# Nixie.net
KiCad netlist of a schematic drawn in Altium Designer
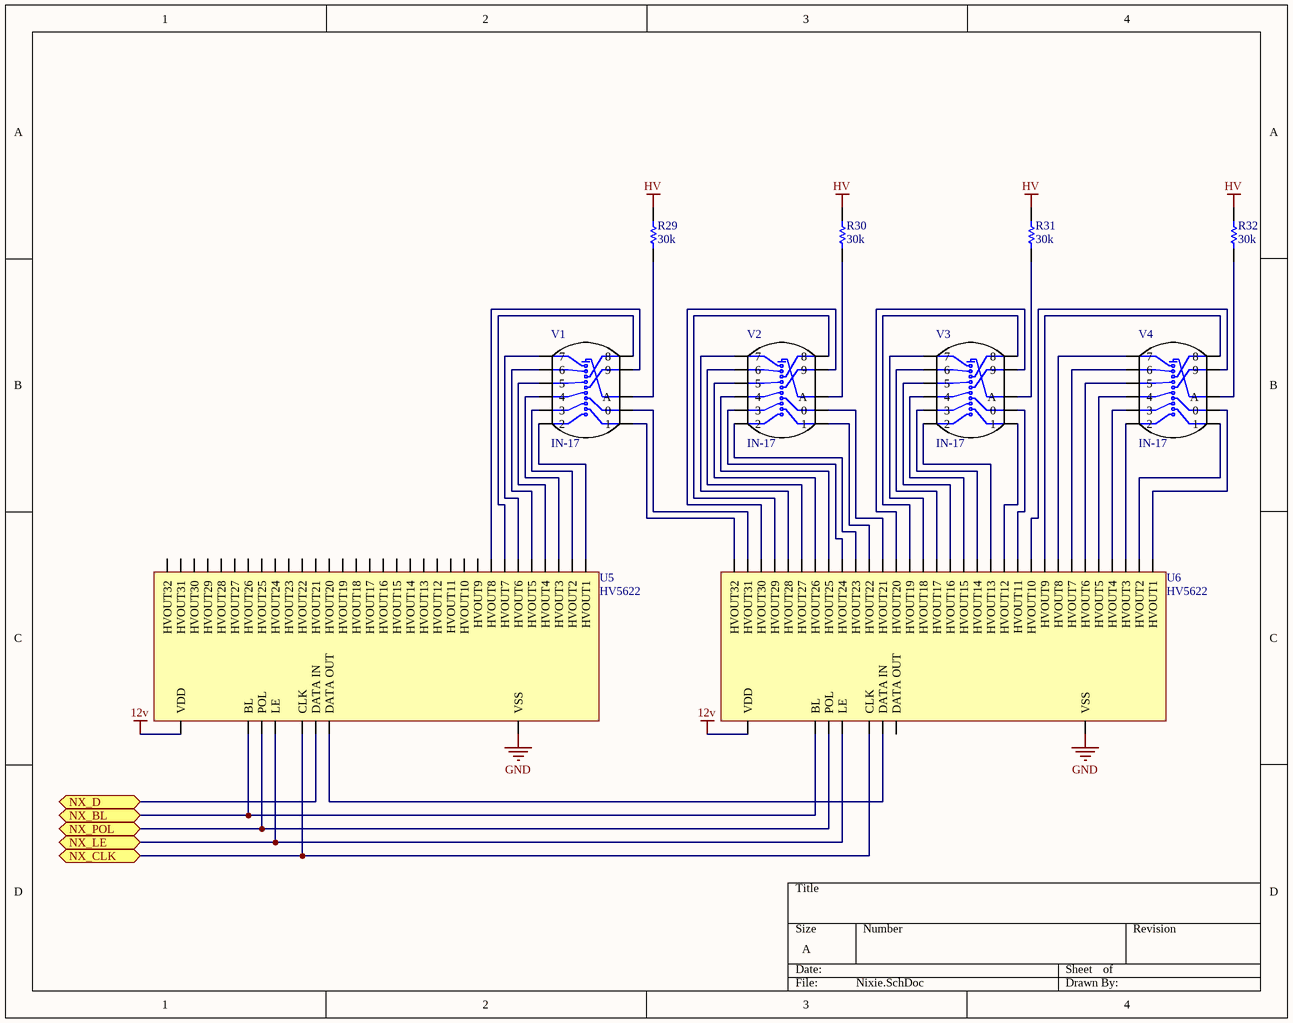
[diagram p0: Nixie.SchDoc]

(export (version "E")
  (design (tool "Eeschema 10.0.6"))
  (components
    (comp (ref "R29")
      (value "30k")
      (footprint "R0805")
      (description "RES SMD 30K OHM 5% 1/8W 0805")
      (libsource (lib "Schlib1") (part "30k 0805 5%"))
    )
    (comp (ref "R30")
      (value "30k")
      (footprint "R0805")
      (description "RES SMD 30K OHM 5% 1/8W 0805")
      (libsource (lib "Schlib1") (part "30k 0805 5%"))
    )
    (comp (ref "R31")
      (value "30k")
      (footprint "R0805")
      (description "RES SMD 30K OHM 5% 1/8W 0805")
      (libsource (lib "Schlib1") (part "30k 0805 5%"))
    )
    (comp (ref "R32")
      (value "30k")
      (footprint "R0805")
      (description "RES SMD 30K OHM 5% 1/8W 0805")
      (libsource (lib "Schlib1") (part "30k 0805 5%"))
    )
    (comp (ref "U5")
      (value "HV5622")
      (footprint "44-PQFP")
      (description "IC 32BIT SRL PARALLEL 220V 44PQF")
      (libsource (lib "Schlib1") (part "HV5622"))
    )
    (comp (ref "U6")
      (value "HV5622")
      (footprint "44-PQFP")
      (description "IC 32BIT SRL PARALLEL 220V 44PQF")
      (libsource (lib "Schlib1") (part "HV5622"))
    )
    (comp (ref "V1")
      (value "IN-17")
      (footprint "IN-17")
      (description "IN-17 Nixie Display Tube")
      (libsource (lib "Schlib1") (part "IN-17 Nixie"))
    )
    (comp (ref "V2")
      (value "IN-17")
      (footprint "IN-17")
      (description "IN-17 Nixie Display Tube")
      (libsource (lib "Schlib1") (part "IN-17 Nixie"))
    )
    (comp (ref "V3")
      (value "IN-17")
      (footprint "IN-17")
      (description "IN-17 Nixie Display Tube")
      (libsource (lib "Schlib1") (part "IN-17 Nixie"))
    )
    (comp (ref "V4")
      (value "IN-17")
      (footprint "IN-17")
      (description "IN-17 Nixie Display Tube")
      (libsource (lib "Schlib1") (part "IN-17 Nixie"))
    )
  )
  (nets
    (net (code "1") (name "/NX_BL") (class "Default")
      (node (ref "U5") (pin "33") (pinfunction "BL_33") (pintype "passive"))
      (node (ref "U6") (pin "33") (pinfunction "BL_33") (pintype "passive"))
    )
    (net (code "2") (name "/NX_CLK") (class "Default")
      (node (ref "U5") (pin "28") (pinfunction "CLK_28") (pintype "passive"))
      (node (ref "U6") (pin "28") (pinfunction "CLK_28") (pintype "passive"))
    )
    (net (code "3") (name "/NX_D") (class "Default")
      (node (ref "U5") (pin "32") (pinfunction "DATA_IN_32") (pintype "passive"))
    )
    (net (code "4") (name "/NX_LE") (class "Default")
      (node (ref "U5") (pin "31") (pinfunction "LE_31") (pintype "passive"))
      (node (ref "U6") (pin "31") (pinfunction "LE_31") (pintype "passive"))
    )
    (net (code "5") (name "/NX_POL") (class "Default")
      (node (ref "U5") (pin "27") (pinfunction "POL_27") (pintype "passive"))
      (node (ref "U6") (pin "27") (pinfunction "POL_27") (pintype "passive"))
    )
    (net (code "6") (name "12v") (class "Default")
      (node (ref "U5") (pin "30") (pinfunction "VDD_30") (pintype "passive"))
      (node (ref "U6") (pin "30") (pinfunction "VDD_30") (pintype "passive"))
    )
    (net (code "7") (name "GND") (class "Default")
      (node (ref "U5") (pin "29") (pinfunction "VSS_29") (pintype "passive"))
      (node (ref "U6") (pin "29") (pinfunction "VSS_29") (pintype "passive"))
    )
    (net (code "8") (name "HV") (class "Default")
      (node (ref "R29") (pin "2") (pinfunction "2_2") (pintype "passive"))
      (node (ref "R30") (pin "2") (pinfunction "2_2") (pintype "passive"))
      (node (ref "R31") (pin "2") (pinfunction "2_2") (pintype "passive"))
      (node (ref "R32") (pin "2") (pinfunction "2_2") (pintype "passive"))
    )
    (net (code "9") (name "Net-(U5-DATA_OUT)") (class "Default")
      (node (ref "U5") (pin "23") (pinfunction "DATA_OUT_23") (pintype "passive"))
      (node (ref "U6") (pin "32") (pinfunction "DATA_IN_32") (pintype "passive"))
    )
    (net (code "10") (name "Net-(U5-HVOUT1)") (class "Default")
      (node (ref "U5") (pin "22") (pinfunction "HVOUT1_22") (pintype "passive"))
      (node (ref "V1") (pin "4") (pinfunction "2_4") (pintype "passive"))
    )
    (net (code "11") (name "Net-(U5-HVOUT2)") (class "Default")
      (node (ref "U5") (pin "21") (pinfunction "HVOUT2_21") (pintype "passive"))
      (node (ref "V1") (pin "5") (pinfunction "3_5") (pintype "passive"))
    )
    (net (code "12") (name "Net-(U5-HVOUT3)") (class "Default")
      (node (ref "U5") (pin "20") (pinfunction "HVOUT3_20") (pintype "passive"))
      (node (ref "V1") (pin "6") (pinfunction "4_6") (pintype "passive"))
    )
    (net (code "13") (name "Net-(U5-HVOUT4)") (class "Default")
      (node (ref "U5") (pin "19") (pinfunction "HVOUT4_19") (pintype "passive"))
      (node (ref "V1") (pin "7") (pinfunction "5_7") (pintype "passive"))
    )
    (net (code "14") (name "Net-(U5-HVOUT5)") (class "Default")
      (node (ref "U5") (pin "18") (pinfunction "HVOUT5_18") (pintype "passive"))
      (node (ref "V1") (pin "8") (pinfunction "6_8") (pintype "passive"))
    )
    (net (code "15") (name "Net-(U5-HVOUT6)") (class "Default")
      (node (ref "U5") (pin "17") (pinfunction "HVOUT6_17") (pintype "passive"))
      (node (ref "V1") (pin "9") (pinfunction "7_9") (pintype "passive"))
    )
    (net (code "16") (name "Net-(U5-HVOUT7)") (class "Default")
      (node (ref "U5") (pin "16") (pinfunction "HVOUT7_16") (pintype "passive"))
      (node (ref "V1") (pin "10") (pinfunction "8_10") (pintype "passive"))
    )
    (net (code "17") (name "Net-(U5-HVOUT8)") (class "Default")
      (node (ref "U5") (pin "15") (pinfunction "HVOUT8_15") (pintype "passive"))
      (node (ref "V1") (pin "11") (pinfunction "9_11") (pintype "passive"))
    )
    (net (code "18") (name "Net-(U6-HVOUT1)") (class "Default")
      (node (ref "U6") (pin "22") (pinfunction "HVOUT1_22") (pintype "passive"))
      (node (ref "V4") (pin "2") (pinfunction "0_2") (pintype "passive"))
    )
    (net (code "19") (name "Net-(U6-HVOUT2)") (class "Default")
      (node (ref "U6") (pin "21") (pinfunction "HVOUT2_21") (pintype "passive"))
      (node (ref "V4") (pin "3") (pinfunction "1_3") (pintype "passive"))
    )
    (net (code "20") (name "Net-(U6-HVOUT3)") (class "Default")
      (node (ref "U6") (pin "20") (pinfunction "HVOUT3_20") (pintype "passive"))
      (node (ref "V4") (pin "4") (pinfunction "2_4") (pintype "passive"))
    )
    (net (code "21") (name "Net-(U6-HVOUT4)") (class "Default")
      (node (ref "U6") (pin "19") (pinfunction "HVOUT4_19") (pintype "passive"))
      (node (ref "V4") (pin "5") (pinfunction "3_5") (pintype "passive"))
    )
    (net (code "22") (name "Net-(U6-HVOUT5)") (class "Default")
      (node (ref "U6") (pin "18") (pinfunction "HVOUT5_18") (pintype "passive"))
      (node (ref "V4") (pin "6") (pinfunction "4_6") (pintype "passive"))
    )
    (net (code "23") (name "Net-(U6-HVOUT6)") (class "Default")
      (node (ref "U6") (pin "17") (pinfunction "HVOUT6_17") (pintype "passive"))
      (node (ref "V4") (pin "7") (pinfunction "5_7") (pintype "passive"))
    )
    (net (code "24") (name "Net-(U6-HVOUT7)") (class "Default")
      (node (ref "U6") (pin "16") (pinfunction "HVOUT7_16") (pintype "passive"))
      (node (ref "V4") (pin "8") (pinfunction "6_8") (pintype "passive"))
    )
    (net (code "25") (name "Net-(U6-HVOUT8)") (class "Default")
      (node (ref "U6") (pin "15") (pinfunction "HVOUT8_15") (pintype "passive"))
      (node (ref "V4") (pin "9") (pinfunction "7_9") (pintype "passive"))
    )
    (net (code "26") (name "Net-(U6-HVOUT9)") (class "Default")
      (node (ref "U6") (pin "14") (pinfunction "HVOUT9_14") (pintype "passive"))
      (node (ref "V4") (pin "10") (pinfunction "8_10") (pintype "passive"))
    )
    (net (code "27") (name "Net-(U6-HVOUT10)") (class "Default")
      (node (ref "U6") (pin "13") (pinfunction "HVOUT10_13") (pintype "passive"))
      (node (ref "V4") (pin "11") (pinfunction "9_11") (pintype "passive"))
    )
    (net (code "28") (name "Net-(U6-HVOUT11)") (class "Default")
      (node (ref "U6") (pin "12") (pinfunction "HVOUT11_12") (pintype "passive"))
      (node (ref "V3") (pin "2") (pinfunction "0_2") (pintype "passive"))
    )
    (net (code "29") (name "Net-(U6-HVOUT12)") (class "Default")
      (node (ref "U6") (pin "11") (pinfunction "HVOUT12_11") (pintype "passive"))
      (node (ref "V3") (pin "3") (pinfunction "1_3") (pintype "passive"))
    )
    (net (code "30") (name "Net-(U6-HVOUT13)") (class "Default")
      (node (ref "U6") (pin "10") (pinfunction "HVOUT13_10") (pintype "passive"))
      (node (ref "V3") (pin "4") (pinfunction "2_4") (pintype "passive"))
    )
    (net (code "31") (name "Net-(U6-HVOUT14)") (class "Default")
      (node (ref "U6") (pin "9") (pinfunction "HVOUT14_9") (pintype "passive"))
      (node (ref "V3") (pin "5") (pinfunction "3_5") (pintype "passive"))
    )
    (net (code "32") (name "Net-(U6-HVOUT15)") (class "Default")
      (node (ref "U6") (pin "8") (pinfunction "HVOUT15_8") (pintype "passive"))
      (node (ref "V3") (pin "6") (pinfunction "4_6") (pintype "passive"))
    )
    (net (code "33") (name "Net-(U6-HVOUT16)") (class "Default")
      (node (ref "U6") (pin "7") (pinfunction "HVOUT16_7") (pintype "passive"))
      (node (ref "V3") (pin "7") (pinfunction "5_7") (pintype "passive"))
    )
    (net (code "34") (name "Net-(U6-HVOUT17)") (class "Default")
      (node (ref "U6") (pin "6") (pinfunction "HVOUT17_6") (pintype "passive"))
      (node (ref "V3") (pin "8") (pinfunction "6_8") (pintype "passive"))
    )
    (net (code "35") (name "Net-(U6-HVOUT18)") (class "Default")
      (node (ref "U6") (pin "5") (pinfunction "HVOUT18_5") (pintype "passive"))
      (node (ref "V3") (pin "9") (pinfunction "7_9") (pintype "passive"))
    )
    (net (code "36") (name "Net-(U6-HVOUT19)") (class "Default")
      (node (ref "U6") (pin "4") (pinfunction "HVOUT19_4") (pintype "passive"))
      (node (ref "V3") (pin "10") (pinfunction "8_10") (pintype "passive"))
    )
    (net (code "37") (name "Net-(U6-HVOUT20)") (class "Default")
      (node (ref "U6") (pin "3") (pinfunction "HVOUT20_3") (pintype "passive"))
      (node (ref "V3") (pin "11") (pinfunction "9_11") (pintype "passive"))
    )
    (net (code "38") (name "Net-(U6-HVOUT21)") (class "Default")
      (node (ref "U6") (pin "2") (pinfunction "HVOUT21_2") (pintype "passive"))
      (node (ref "V2") (pin "2") (pinfunction "0_2") (pintype "passive"))
    )
    (net (code "39") (name "Net-(U6-HVOUT22)") (class "Default")
      (node (ref "U6") (pin "1") (pinfunction "HVOUT22_1") (pintype "passive"))
      (node (ref "V2") (pin "3") (pinfunction "1_3") (pintype "passive"))
    )
    (net (code "40") (name "Net-(U6-HVOUT23)") (class "Default")
      (node (ref "U6") (pin "44") (pinfunction "HVOUT23_44") (pintype "passive"))
      (node (ref "V2") (pin "4") (pinfunction "2_4") (pintype "passive"))
    )
    (net (code "41") (name "Net-(U6-HVOUT24)") (class "Default")
      (node (ref "U6") (pin "43") (pinfunction "HVOUT24_43") (pintype "passive"))
      (node (ref "V2") (pin "5") (pinfunction "3_5") (pintype "passive"))
    )
    (net (code "42") (name "Net-(U6-HVOUT25)") (class "Default")
      (node (ref "U6") (pin "42") (pinfunction "HVOUT25_42") (pintype "passive"))
      (node (ref "V2") (pin "6") (pinfunction "4_6") (pintype "passive"))
    )
    (net (code "43") (name "Net-(U6-HVOUT26)") (class "Default")
      (node (ref "U6") (pin "41") (pinfunction "HVOUT26_41") (pintype "passive"))
      (node (ref "V2") (pin "7") (pinfunction "5_7") (pintype "passive"))
    )
    (net (code "44") (name "Net-(U6-HVOUT27)") (class "Default")
      (node (ref "U6") (pin "40") (pinfunction "HVOUT27_40") (pintype "passive"))
      (node (ref "V2") (pin "8") (pinfunction "6_8") (pintype "passive"))
    )
    (net (code "45") (name "Net-(U6-HVOUT28)") (class "Default")
      (node (ref "U6") (pin "39") (pinfunction "HVOUT28_39") (pintype "passive"))
      (node (ref "V2") (pin "9") (pinfunction "7_9") (pintype "passive"))
    )
    (net (code "46") (name "Net-(U6-HVOUT29)") (class "Default")
      (node (ref "U6") (pin "38") (pinfunction "HVOUT29_38") (pintype "passive"))
      (node (ref "V2") (pin "10") (pinfunction "8_10") (pintype "passive"))
    )
    (net (code "47") (name "Net-(U6-HVOUT30)") (class "Default")
      (node (ref "U6") (pin "37") (pinfunction "HVOUT30_37") (pintype "passive"))
      (node (ref "V2") (pin "11") (pinfunction "9_11") (pintype "passive"))
    )
    (net (code "48") (name "Net-(U6-HVOUT31)") (class "Default")
      (node (ref "U6") (pin "36") (pinfunction "HVOUT31_36") (pintype "passive"))
      (node (ref "V1") (pin "2") (pinfunction "0_2") (pintype "passive"))
    )
    (net (code "49") (name "Net-(U6-HVOUT32)") (class "Default")
      (node (ref "U6") (pin "35") (pinfunction "HVOUT32_35") (pintype "passive"))
      (node (ref "V1") (pin "3") (pinfunction "1_3") (pintype "passive"))
    )
    (net (code "50") (name "Net-(V1-A)") (class "Default")
      (node (ref "R29") (pin "1") (pinfunction "1_1") (pintype "passive"))
      (node (ref "V1") (pin "1") (pinfunction "A_1") (pintype "passive"))
    )
    (net (code "51") (name "Net-(V2-A)") (class "Default")
      (node (ref "R30") (pin "1") (pinfunction "1_1") (pintype "passive"))
      (node (ref "V2") (pin "1") (pinfunction "A_1") (pintype "passive"))
    )
    (net (code "52") (name "Net-(V3-A)") (class "Default")
      (node (ref "R31") (pin "1") (pinfunction "1_1") (pintype "passive"))
      (node (ref "V3") (pin "1") (pinfunction "A_1") (pintype "passive"))
    )
    (net (code "53") (name "Net-(V4-A)") (class "Default")
      (node (ref "R32") (pin "1") (pinfunction "1_1") (pintype "passive"))
      (node (ref "V4") (pin "1") (pinfunction "A_1") (pintype "passive"))
    )
    (net (code "54") (name "unconnected-(U5-HVOUT9-Pad14)") (class "Default")
      (node (ref "U5") (pin "14") (pinfunction "HVOUT9_14") (pintype "passive"))
    )
    (net (code "55") (name "unconnected-(U5-HVOUT10-Pad13)") (class "Default")
      (node (ref "U5") (pin "13") (pinfunction "HVOUT10_13") (pintype "passive"))
    )
    (net (code "56") (name "unconnected-(U5-HVOUT11-Pad12)") (class "Default")
      (node (ref "U5") (pin "12") (pinfunction "HVOUT11_12") (pintype "passive"))
    )
    (net (code "57") (name "unconnected-(U5-HVOUT12-Pad11)") (class "Default")
      (node (ref "U5") (pin "11") (pinfunction "HVOUT12_11") (pintype "passive"))
    )
    (net (code "58") (name "unconnected-(U5-HVOUT13-Pad10)") (class "Default")
      (node (ref "U5") (pin "10") (pinfunction "HVOUT13_10") (pintype "passive"))
    )
    (net (code "59") (name "unconnected-(U5-HVOUT14-Pad9)") (class "Default")
      (node (ref "U5") (pin "9") (pinfunction "HVOUT14_9") (pintype "passive"))
    )
    (net (code "60") (name "unconnected-(U5-HVOUT15-Pad8)") (class "Default")
      (node (ref "U5") (pin "8") (pinfunction "HVOUT15_8") (pintype "passive"))
    )
    (net (code "61") (name "unconnected-(U5-HVOUT16-Pad7)") (class "Default")
      (node (ref "U5") (pin "7") (pinfunction "HVOUT16_7") (pintype "passive"))
    )
    (net (code "62") (name "unconnected-(U5-HVOUT17-Pad6)") (class "Default")
      (node (ref "U5") (pin "6") (pinfunction "HVOUT17_6") (pintype "passive"))
    )
    (net (code "63") (name "unconnected-(U5-HVOUT18-Pad5)") (class "Default")
      (node (ref "U5") (pin "5") (pinfunction "HVOUT18_5") (pintype "passive"))
    )
    (net (code "64") (name "unconnected-(U5-HVOUT19-Pad4)") (class "Default")
      (node (ref "U5") (pin "4") (pinfunction "HVOUT19_4") (pintype "passive"))
    )
    (net (code "65") (name "unconnected-(U5-HVOUT20-Pad3)") (class "Default")
      (node (ref "U5") (pin "3") (pinfunction "HVOUT20_3") (pintype "passive"))
    )
    (net (code "66") (name "unconnected-(U5-HVOUT21-Pad2)") (class "Default")
      (node (ref "U5") (pin "2") (pinfunction "HVOUT21_2") (pintype "passive"))
    )
    (net (code "67") (name "unconnected-(U5-HVOUT22-Pad1)") (class "Default")
      (node (ref "U5") (pin "1") (pinfunction "HVOUT22_1") (pintype "passive"))
    )
    (net (code "68") (name "unconnected-(U5-HVOUT23-Pad44)") (class "Default")
      (node (ref "U5") (pin "44") (pinfunction "HVOUT23_44") (pintype "passive"))
    )
    (net (code "69") (name "unconnected-(U5-HVOUT24-Pad43)") (class "Default")
      (node (ref "U5") (pin "43") (pinfunction "HVOUT24_43") (pintype "passive"))
    )
    (net (code "70") (name "unconnected-(U5-HVOUT25-Pad42)") (class "Default")
      (node (ref "U5") (pin "42") (pinfunction "HVOUT25_42") (pintype "passive"))
    )
    (net (code "71") (name "unconnected-(U5-HVOUT26-Pad41)") (class "Default")
      (node (ref "U5") (pin "41") (pinfunction "HVOUT26_41") (pintype "passive"))
    )
    (net (code "72") (name "unconnected-(U5-HVOUT27-Pad40)") (class "Default")
      (node (ref "U5") (pin "40") (pinfunction "HVOUT27_40") (pintype "passive"))
    )
    (net (code "73") (name "unconnected-(U5-HVOUT28-Pad39)") (class "Default")
      (node (ref "U5") (pin "39") (pinfunction "HVOUT28_39") (pintype "passive"))
    )
    (net (code "74") (name "unconnected-(U5-HVOUT29-Pad38)") (class "Default")
      (node (ref "U5") (pin "38") (pinfunction "HVOUT29_38") (pintype "passive"))
    )
    (net (code "75") (name "unconnected-(U5-HVOUT30-Pad37)") (class "Default")
      (node (ref "U5") (pin "37") (pinfunction "HVOUT30_37") (pintype "passive"))
    )
    (net (code "76") (name "unconnected-(U5-HVOUT31-Pad36)") (class "Default")
      (node (ref "U5") (pin "36") (pinfunction "HVOUT31_36") (pintype "passive"))
    )
    (net (code "77") (name "unconnected-(U5-HVOUT32-Pad35)") (class "Default")
      (node (ref "U5") (pin "35") (pinfunction "HVOUT32_35") (pintype "passive"))
    )
    (net (code "78") (name "unconnected-(U6-DATA_OUT-Pad23)") (class "Default")
      (node (ref "U6") (pin "23") (pinfunction "DATA_OUT_23") (pintype "passive"))
    )
  )
)
